# Charge-Pump-Shield.net
KiCad netlist of a schematic drawn in Altium Designer
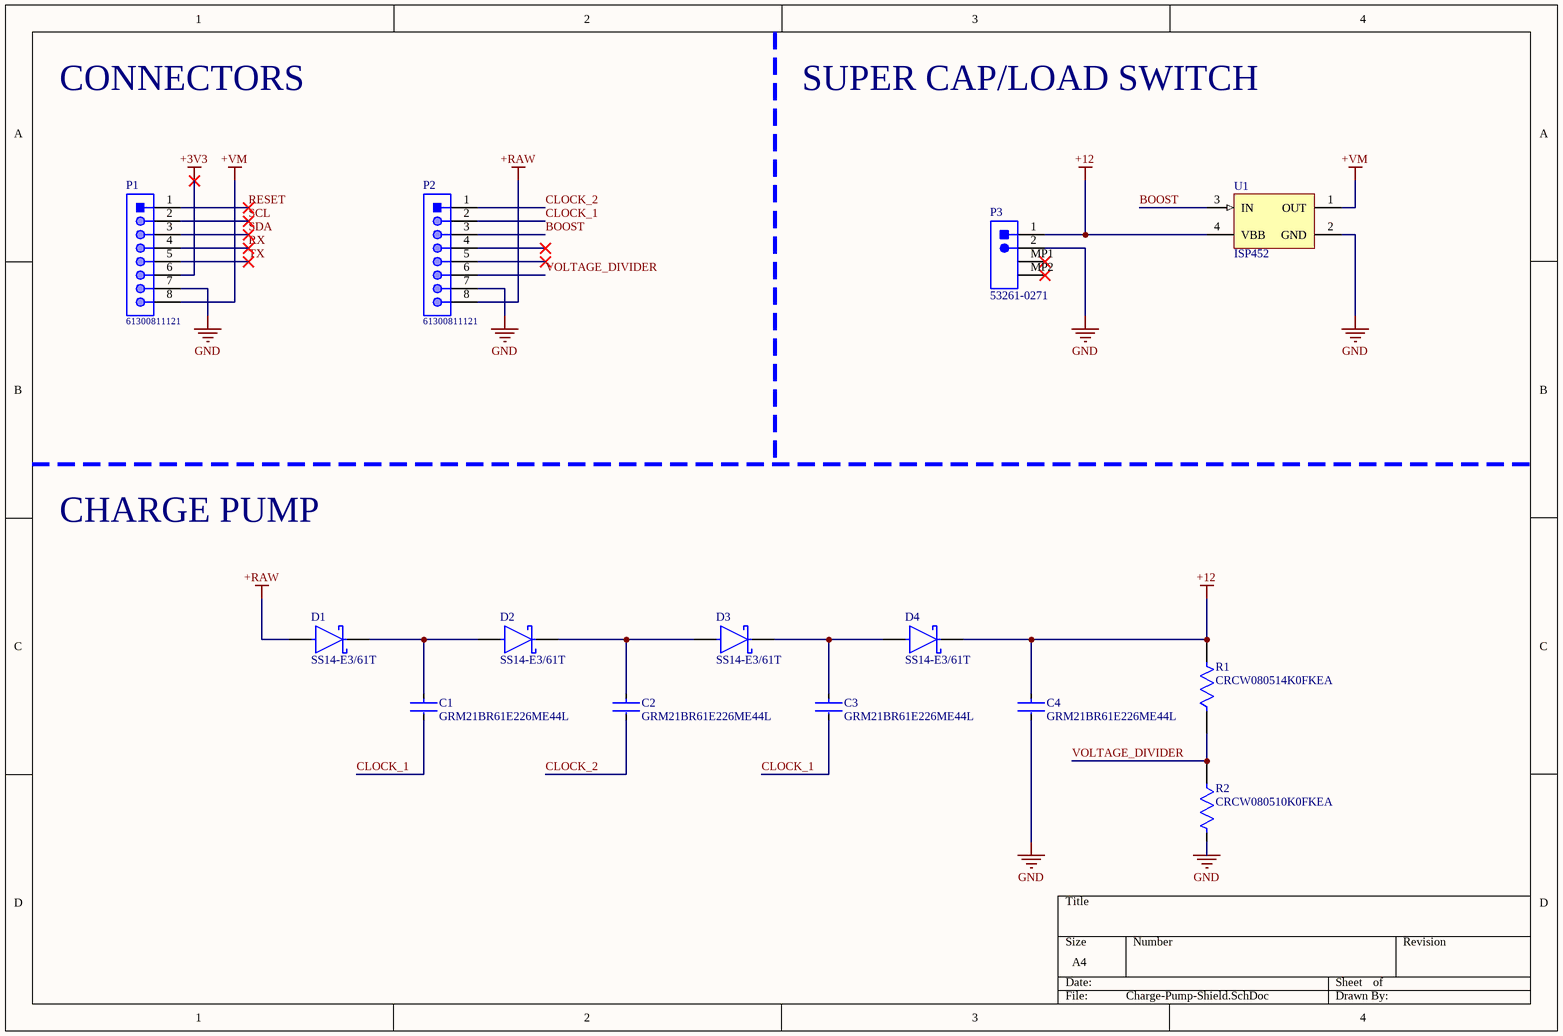
[diagram p0: Charge-Pump-Shield.SchDoc]

(export (version "E")
  (design (tool "Eeschema 10.0.6"))
  (components
    (comp (ref "C1")
      (value "GRM21BR61E226ME44L")
      (footprint "FP-GRM21B-0_2-e0_2_0_7-IPC_B")
      (description "Chip Multilayer Ceramic Capacitors for General Purpose, 0805, 22uF, X5R, 15%, 20%, 25V")
      (fields (field (name "TOLERANCE") "20%") (field (name "VOLTAGE") "25V"))
      (libsource (lib "Altium Content Vault") (part "b4654b650e69147ec39a6b967a45e02"))
    )
    (comp (ref "C2")
      (value "GRM21BR61E226ME44L")
      (footprint "FP-GRM21B-0_2-e0_2_0_7-IPC_B")
      (description "Chip Multilayer Ceramic Capacitors for General Purpose, 0805, 22uF, X5R, 15%, 20%, 25V")
      (fields (field (name "TOLERANCE") "20%") (field (name "VOLTAGE") "25V"))
      (libsource (lib "Altium Content Vault") (part "b4654b650e69147ec39a6b967a45e02"))
    )
    (comp (ref "C3")
      (value "GRM21BR61E226ME44L")
      (footprint "FP-GRM21B-0_2-e0_2_0_7-IPC_B")
      (description "Chip Multilayer Ceramic Capacitors for General Purpose, 0805, 22uF, X5R, 15%, 20%, 25V")
      (fields (field (name "TOLERANCE") "20%") (field (name "VOLTAGE") "25V"))
      (libsource (lib "Altium Content Vault") (part "b4654b650e69147ec39a6b967a45e02"))
    )
    (comp (ref "C4")
      (value "GRM21BR61E226ME44L")
      (footprint "FP-GRM21B-0_2-e0_2_0_7-IPC_B")
      (description "Chip Multilayer Ceramic Capacitors for General Purpose, 0805, 22uF, X5R, 15%, 20%, 25V")
      (fields (field (name "TOLERANCE") "20%") (field (name "VOLTAGE") "25V"))
      (libsource (lib "Altium Content Vault") (part "b4654b650e69147ec39a6b967a45e02"))
    )
    (comp (ref "D1")
      (value "SS14-E3/61T")
      (footprint "FP-95400-MFG")
      (description "DIODE SCHOTTKY 40V 1A DO214AC")
      (fields
        (field (name "OCTOPART") "https://octopart.com/ss14-e3%2F61t-vishay-39552847")
        (field (name "MANUFACTURER") "Vishay")
      )
      (libsource (lib "Altium Content Vault") (part "1d6ec82d83fb6aee721767c19dac4b9"))
    )
    (comp (ref "D2")
      (value "SS14-E3/61T")
      (footprint "FP-95400-MFG")
      (description "DIODE SCHOTTKY 40V 1A DO214AC")
      (fields
        (field (name "OCTOPART") "https://octopart.com/ss14-e3%2F61t-vishay-39552847")
        (field (name "MANUFACTURER") "Vishay")
      )
      (libsource (lib "Altium Content Vault") (part "1d6ec82d83fb6aee721767c19dac4b9"))
    )
    (comp (ref "D3")
      (value "SS14-E3/61T")
      (footprint "FP-95400-MFG")
      (description "DIODE SCHOTTKY 40V 1A DO214AC")
      (fields
        (field (name "OCTOPART") "https://octopart.com/ss14-e3%2F61t-vishay-39552847")
        (field (name "MANUFACTURER") "Vishay")
      )
      (libsource (lib "Altium Content Vault") (part "1d6ec82d83fb6aee721767c19dac4b9"))
    )
    (comp (ref "D4")
      (value "SS14-E3/61T")
      (footprint "FP-95400-MFG")
      (description "DIODE SCHOTTKY 40V 1A DO214AC")
      (fields
        (field (name "OCTOPART") "https://octopart.com/ss14-e3%2F61t-vishay-39552847")
        (field (name "MANUFACTURER") "Vishay")
      )
      (libsource (lib "Altium Content Vault") (part "1d6ec82d83fb6aee721767c19dac4b9"))
    )
    (comp (ref "P1")
      (value "61300811121")
      (footprint "61300811121")
      (description "THT Vertical Pin Header WR-PHD, Pitch 2.54 mm, Single Row, 8 pins")
      (fields (field (name "MANUFACTURER") "Wurth Elektronik") (field (name "PUBLISHER") "WurthElektronik"))
      (libsource (lib "Altium Content Vault") (part "WE-CN-1P-M-R8"))
    )
    (comp (ref "P2")
      (value "61300811121")
      (footprint "61300811121")
      (description "THT Vertical Pin Header WR-PHD, Pitch 2.54 mm, Single Row, 8 pins")
      (fields (field (name "MANUFACTURER") "Wurth Elektronik") (field (name "PUBLISHER") "WurthElektronik"))
      (libsource (lib "Altium Content Vault") (part "WE-CN-1P-M-R8"))
    )
    (comp (ref "P3")
      (value "53261-0271")
      (footprint "MOLX-53261-0271_V")
      (description "PicoBlade(TM) Header, Right Angle, -40 to 85 degC, 2-Pin SMD, RoHS, Tape and Reel")
      (fields (field (name "MANUFACTURER") "Molex"))
      (libsource (lib "Altium Content Vault") (part "CN-1P-2M-R2"))
    )
    (comp (ref "R1")
      (value "CRCW080514K0FKEA")
      (footprint "FP-CRCW0805-e3-MFG")
      (description "RES Thick Film, 14kΩ, 1%, 0.125W, 100ppm/°C, 0805")
      (fields (field (name "TOLERANCE") "1%"))
      (libsource (lib "Altium Content Vault") (part "1029c3af85768c4190bb7ad29bc67b5"))
    )
    (comp (ref "R2")
      (value "CRCW080510K0FKEA")
      (footprint "FP-CRCW0805-e3-IPC_A")
      (description "RES Thick Film, 10kΩ, 1%, 0.125W, 100ppm/°C, 0805")
      (fields (field (name "TOLERANCE") "1%"))
      (libsource (lib "Altium Content Vault") (part "1029c3af85768c4190bb7ad29bc67b5"))
    )
    (comp (ref "U1")
      (value "ISP452")
      (footprint "INF-SOT223_L")
      (fields (field (name "MANUFACTURER") "Infineon"))
      (libsource (lib "Altium Content Vault") (part "INF-ISP452-SOT223-4"))
    )
  )
  (nets
    (net (code "1") (name "+3V3") (class "Default")
      (node (ref "P1") (pin "6") (pinfunction "6_6") (pintype "passive"))
    )
    (net (code "2") (name "+12") (class "Default")
      (node (ref "C4") (pin "1") (pinfunction "1_1") (pintype "passive"))
      (node (ref "D4") (pin "1") (pinfunction "C_1") (pintype "passive"))
      (node (ref "P3") (pin "1") (pinfunction "1_1") (pintype "passive"))
      (node (ref "R1") (pin "2") (pinfunction "2_2") (pintype "passive"))
      (node (ref "U1") (pin "4") (pinfunction "VBB_4") (pintype "power_in"))
    )
    (net (code "3") (name "+RAW") (class "Default")
      (node (ref "D1") (pin "2") (pinfunction "A_2") (pintype "passive"))
      (node (ref "P2") (pin "8") (pinfunction "8_8") (pintype "passive"))
    )
    (net (code "4") (name "+VM") (class "Default")
      (node (ref "P1") (pin "8") (pinfunction "8_8") (pintype "passive"))
      (node (ref "U1") (pin "1") (pinfunction "OUT_1") (pintype "power_in"))
    )
    (net (code "5") (name "/BOOST") (class "Default")
      (node (ref "P2") (pin "3") (pinfunction "3_3") (pintype "passive"))
      (node (ref "U1") (pin "3") (pinfunction "IN_3") (pintype "input"))
    )
    (net (code "6") (name "/CLOCK_1") (class "Default")
      (node (ref "C1") (pin "2") (pinfunction "2_2") (pintype "passive"))
      (node (ref "C3") (pin "2") (pinfunction "2_2") (pintype "passive"))
      (node (ref "P2") (pin "2") (pinfunction "2_2") (pintype "passive"))
    )
    (net (code "7") (name "/CLOCK_2") (class "Default")
      (node (ref "C2") (pin "2") (pinfunction "2_2") (pintype "passive"))
      (node (ref "P2") (pin "1") (pinfunction "1_1") (pintype "passive"))
    )
    (net (code "8") (name "/RESET") (class "Default")
      (node (ref "P1") (pin "1") (pinfunction "1_1") (pintype "passive+no_connect"))
    )
    (net (code "9") (name "/RX") (class "Default")
      (node (ref "P1") (pin "4") (pinfunction "4_4") (pintype "passive+no_connect"))
    )
    (net (code "10") (name "/SCL") (class "Default")
      (node (ref "P1") (pin "2") (pinfunction "2_2") (pintype "passive+no_connect"))
    )
    (net (code "11") (name "/SDA") (class "Default")
      (node (ref "P1") (pin "3") (pinfunction "3_3") (pintype "passive+no_connect"))
    )
    (net (code "12") (name "/TX") (class "Default")
      (node (ref "P1") (pin "5") (pinfunction "5_5") (pintype "passive+no_connect"))
    )
    (net (code "13") (name "/VOLTAGE_DIVIDER") (class "Default")
      (node (ref "P2") (pin "6") (pinfunction "6_6") (pintype "passive"))
      (node (ref "R1") (pin "1") (pinfunction "1_1") (pintype "passive"))
      (node (ref "R2") (pin "1") (pinfunction "1_1") (pintype "passive"))
    )
    (net (code "14") (name "GND") (class "Default")
      (node (ref "C4") (pin "2") (pinfunction "2_2") (pintype "passive"))
      (node (ref "P1") (pin "7") (pinfunction "7_7") (pintype "passive"))
      (node (ref "P2") (pin "7") (pinfunction "7_7") (pintype "passive"))
      (node (ref "P3") (pin "2") (pinfunction "2_2") (pintype "passive"))
      (node (ref "R2") (pin "2") (pinfunction "2_2") (pintype "passive"))
      (node (ref "U1") (pin "2") (pinfunction "GND_2") (pintype "power_in"))
    )
    (net (code "15") (name "Net-(D1-C)") (class "Default")
      (node (ref "C1") (pin "1") (pinfunction "1_1") (pintype "passive"))
      (node (ref "D1") (pin "1") (pinfunction "C_1") (pintype "passive"))
      (node (ref "D2") (pin "2") (pinfunction "A_2") (pintype "passive"))
    )
    (net (code "16") (name "Net-(D2-C)") (class "Default")
      (node (ref "C2") (pin "1") (pinfunction "1_1") (pintype "passive"))
      (node (ref "D2") (pin "1") (pinfunction "C_1") (pintype "passive"))
      (node (ref "D3") (pin "2") (pinfunction "A_2") (pintype "passive"))
    )
    (net (code "17") (name "Net-(D3-C)") (class "Default")
      (node (ref "C3") (pin "1") (pinfunction "1_1") (pintype "passive"))
      (node (ref "D3") (pin "1") (pinfunction "C_1") (pintype "passive"))
      (node (ref "D4") (pin "2") (pinfunction "A_2") (pintype "passive"))
    )
    (net (code "18") (name "unconnected-(P2-Pad4)") (class "Default")
      (node (ref "P2") (pin "4") (pinfunction "4_4") (pintype "passive+no_connect"))
    )
    (net (code "19") (name "unconnected-(P2-Pad5)") (class "Default")
      (node (ref "P2") (pin "5") (pinfunction "5_5") (pintype "passive+no_connect"))
    )
    (net (code "20") (name "unconnected-(P3-PadMP1)") (class "Default")
      (node (ref "P3") (pin "MP1") (pinfunction "MP1_MP1") (pintype "passive+no_connect"))
    )
    (net (code "21") (name "unconnected-(P3-PadMP2)") (class "Default")
      (node (ref "P3") (pin "MP2") (pinfunction "MP2_MP2") (pintype "passive+no_connect"))
    )
  )
)
